# 7segement4digits1badidea-shield-mk-3.net
KiCad netlist of a schematic drawn in EAGLE
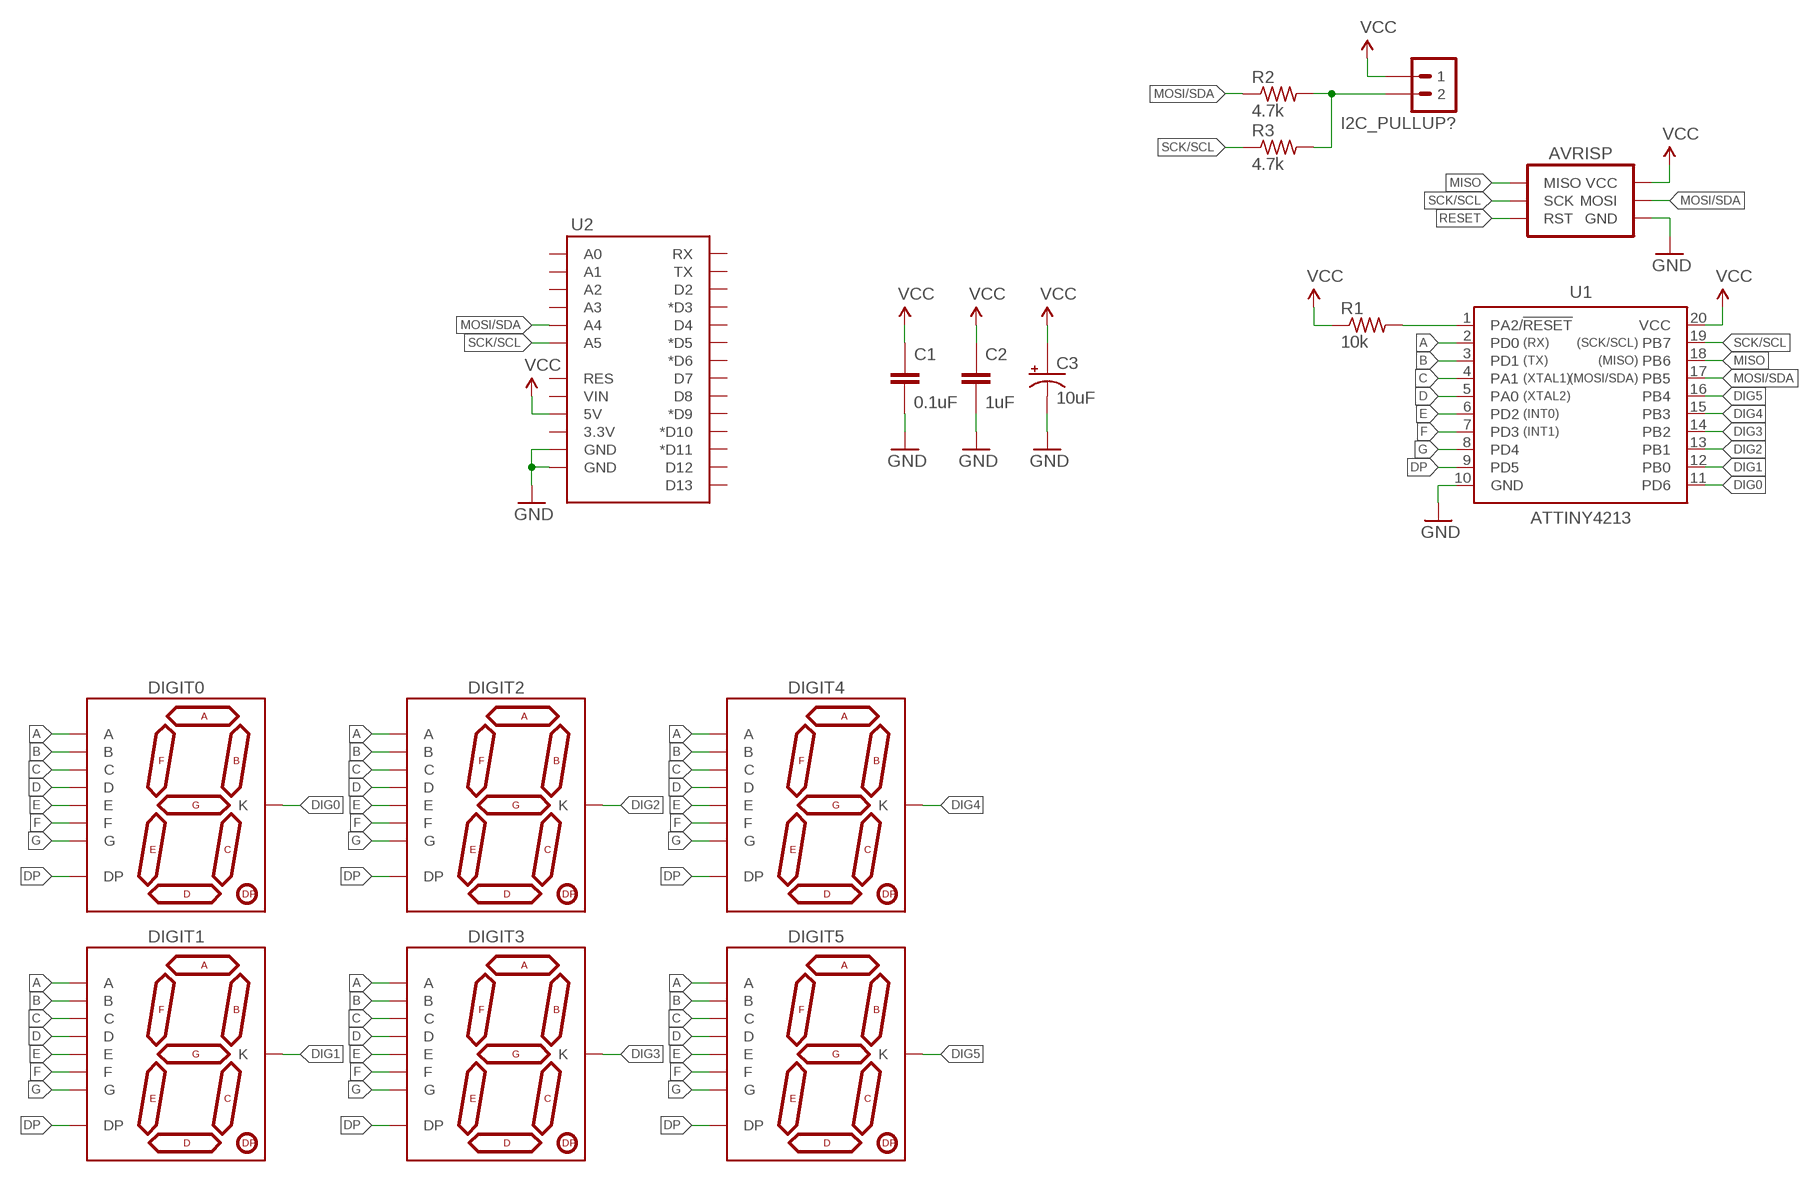
[diagram p0: schematic, sheet 1]

(export (version "E")
  (design (tool "Eeschema 10.0.6"))
  (components
    (comp (ref "AVRISP")
      (value "AVR_SPI_PRG_6PTH")
      (footprint "eagle-import:2X3")
      (libsource (lib "eagle-import") (part "AVR_SPI_PRG_6PTH"))
    )
    (comp (ref "C1")
      (value "0.1uF")
      (footprint "eagle-import:C025-024X044")
      (libsource (lib "eagle-import") (part "CAPACITOR-CERAMIC025-024X044"))
    )
    (comp (ref "C2")
      (value "1uF")
      (footprint "eagle-import:C025-024X044")
      (libsource (lib "eagle-import") (part "CAPACITOR-CERAMIC025-024X044"))
    )
    (comp (ref "C3")
      (value "10uF")
      (footprint "eagle-import:E2,5-5")
      (libsource (lib "eagle-import") (part "CAPACITOR-POLARIZEDE2.5-5"))
    )
    (comp (ref "DIGIT0")
      (value "7SEG_1DIGPTH-10MM")
      (footprint "eagle-import:7SEG_1DIG_10MM")
      (libsource (lib "eagle-import") (part "7SEG_1DIGPTH-10MM"))
    )
    (comp (ref "DIGIT1")
      (value "7SEG_1DIGPTH-10MM")
      (footprint "eagle-import:7SEG_1DIG_10MM")
      (libsource (lib "eagle-import") (part "7SEG_1DIGPTH-10MM"))
    )
    (comp (ref "DIGIT2")
      (value "7SEG_1DIGPTH-10MM")
      (footprint "eagle-import:7SEG_1DIG_10MM")
      (libsource (lib "eagle-import") (part "7SEG_1DIGPTH-10MM"))
    )
    (comp (ref "DIGIT3")
      (value "7SEG_1DIGPTH-10MM")
      (footprint "eagle-import:7SEG_1DIG_10MM")
      (libsource (lib "eagle-import") (part "7SEG_1DIGPTH-10MM"))
    )
    (comp (ref "DIGIT4")
      (value "7SEG_1DIGPTH-10MM")
      (footprint "eagle-import:7SEG_1DIG_10MM")
      (libsource (lib "eagle-import") (part "7SEG_1DIGPTH-10MM"))
    )
    (comp (ref "DIGIT5")
      (value "7SEG_1DIGPTH-10MM")
      (footprint "eagle-import:7SEG_1DIG_10MM")
      (libsource (lib "eagle-import") (part "7SEG_1DIGPTH-10MM"))
    )
    (comp (ref "I2C_PULLUP?")
      (value "M02PTH")
      (footprint "eagle-import:1X02")
      (libsource (lib "eagle-import") (part "M02PTH"))
    )
    (comp (ref "R1")
      (value "10k")
      (footprint "eagle-import:RESISTOR-AXIAL-PTH-7.68MM")
      (libsource (lib "eagle-import") (part "RESISTORPTH-AXIAL-7.68MM"))
    )
    (comp (ref "R2")
      (value "4.7k")
      (footprint "eagle-import:RESISTOR-AXIAL-PTH-7.68MM")
      (libsource (lib "eagle-import") (part "RESISTORPTH-AXIAL-7.68MM"))
    )
    (comp (ref "R3")
      (value "4.7k")
      (footprint "eagle-import:RESISTOR-AXIAL-PTH-7.68MM")
      (libsource (lib "eagle-import") (part "RESISTORPTH-AXIAL-7.68MM"))
    )
    (comp (ref "U1")
      (value "ATTINY4213")
      (footprint "eagle-import:DIL20")
      (libsource (lib "eagle-import") (part "ATTINY2313ADIP"))
    )
    (comp (ref "U2")
      (value "ARDUINO_SHIELD_SMALLER")
      (footprint "eagle-import:ARDUINO_SHIELD_NOOUTLINE_INSIDE_SMALLER")
      (libsource (lib "eagle-import") (part "ARDUINO_SHIELD_SMALLER"))
    )
  )
  (nets
    (net (code "1") (name "A") (class "Default")
      (node (ref "DIGIT0") (pin "10") (pinfunction "A_10") (pintype "bidirectional"))
      (node (ref "DIGIT1") (pin "10") (pinfunction "A_10") (pintype "bidirectional"))
      (node (ref "DIGIT2") (pin "10") (pinfunction "A_10") (pintype "bidirectional"))
      (node (ref "DIGIT3") (pin "10") (pinfunction "A_10") (pintype "bidirectional"))
      (node (ref "DIGIT4") (pin "10") (pinfunction "A_10") (pintype "bidirectional"))
      (node (ref "DIGIT5") (pin "10") (pinfunction "A_10") (pintype "bidirectional"))
      (node (ref "U1") (pin "2") (pinfunction "PD0_2") (pintype "bidirectional"))
    )
    (net (code "2") (name "B") (class "Default")
      (node (ref "DIGIT0") (pin "9") (pinfunction "B_9") (pintype "bidirectional"))
      (node (ref "DIGIT1") (pin "9") (pinfunction "B_9") (pintype "bidirectional"))
      (node (ref "DIGIT2") (pin "9") (pinfunction "B_9") (pintype "bidirectional"))
      (node (ref "DIGIT3") (pin "9") (pinfunction "B_9") (pintype "bidirectional"))
      (node (ref "DIGIT4") (pin "9") (pinfunction "B_9") (pintype "bidirectional"))
      (node (ref "DIGIT5") (pin "9") (pinfunction "B_9") (pintype "bidirectional"))
      (node (ref "U1") (pin "3") (pinfunction "PD1_3") (pintype "bidirectional"))
    )
    (net (code "3") (name "C") (class "Default")
      (node (ref "DIGIT0") (pin "8") (pinfunction "C_8") (pintype "bidirectional"))
      (node (ref "DIGIT1") (pin "8") (pinfunction "C_8") (pintype "bidirectional"))
      (node (ref "DIGIT2") (pin "8") (pinfunction "C_8") (pintype "bidirectional"))
      (node (ref "DIGIT3") (pin "8") (pinfunction "C_8") (pintype "bidirectional"))
      (node (ref "DIGIT4") (pin "8") (pinfunction "C_8") (pintype "bidirectional"))
      (node (ref "DIGIT5") (pin "8") (pinfunction "C_8") (pintype "bidirectional"))
      (node (ref "U1") (pin "4") (pinfunction "PA1_4") (pintype "bidirectional"))
    )
    (net (code "4") (name "D") (class "Default")
      (node (ref "DIGIT0") (pin "5") (pinfunction "D_5") (pintype "bidirectional"))
      (node (ref "DIGIT1") (pin "5") (pinfunction "D_5") (pintype "bidirectional"))
      (node (ref "DIGIT2") (pin "5") (pinfunction "D_5") (pintype "bidirectional"))
      (node (ref "DIGIT3") (pin "5") (pinfunction "D_5") (pintype "bidirectional"))
      (node (ref "DIGIT4") (pin "5") (pinfunction "D_5") (pintype "bidirectional"))
      (node (ref "DIGIT5") (pin "5") (pinfunction "D_5") (pintype "bidirectional"))
      (node (ref "U1") (pin "5") (pinfunction "PA0_5") (pintype "bidirectional"))
    )
    (net (code "5") (name "DIG0") (class "Default")
      (node (ref "DIGIT0") (pin "1") (pinfunction "K_1") (pintype "bidirectional"))
      (node (ref "DIGIT0") (pin "6") (pinfunction "K_6") (pintype "bidirectional"))
      (node (ref "U1") (pin "11") (pinfunction "PD6_11") (pintype "bidirectional"))
    )
    (net (code "6") (name "DIG1") (class "Default")
      (node (ref "DIGIT1") (pin "1") (pinfunction "K_1") (pintype "bidirectional"))
      (node (ref "DIGIT1") (pin "6") (pinfunction "K_6") (pintype "bidirectional"))
      (node (ref "U1") (pin "12") (pinfunction "PB0_12") (pintype "bidirectional"))
    )
    (net (code "7") (name "DIG2") (class "Default")
      (node (ref "DIGIT2") (pin "1") (pinfunction "K_1") (pintype "bidirectional"))
      (node (ref "DIGIT2") (pin "6") (pinfunction "K_6") (pintype "bidirectional"))
      (node (ref "U1") (pin "13") (pinfunction "PB1_13") (pintype "bidirectional"))
    )
    (net (code "8") (name "DIG3") (class "Default")
      (node (ref "DIGIT3") (pin "1") (pinfunction "K_1") (pintype "bidirectional"))
      (node (ref "DIGIT3") (pin "6") (pinfunction "K_6") (pintype "bidirectional"))
      (node (ref "U1") (pin "14") (pinfunction "PB2_14") (pintype "bidirectional"))
    )
    (net (code "9") (name "DIG4") (class "Default")
      (node (ref "DIGIT4") (pin "1") (pinfunction "K_1") (pintype "bidirectional"))
      (node (ref "DIGIT4") (pin "6") (pinfunction "K_6") (pintype "bidirectional"))
      (node (ref "U1") (pin "15") (pinfunction "PB3_15") (pintype "bidirectional"))
    )
    (net (code "10") (name "DIG5") (class "Default")
      (node (ref "DIGIT5") (pin "1") (pinfunction "K_1") (pintype "bidirectional"))
      (node (ref "DIGIT5") (pin "6") (pinfunction "K_6") (pintype "bidirectional"))
      (node (ref "U1") (pin "16") (pinfunction "PB4_16") (pintype "bidirectional"))
    )
    (net (code "11") (name "DP") (class "Default")
      (node (ref "DIGIT0") (pin "7") (pinfunction "DP_7") (pintype "bidirectional"))
      (node (ref "DIGIT1") (pin "7") (pinfunction "DP_7") (pintype "bidirectional"))
      (node (ref "DIGIT2") (pin "7") (pinfunction "DP_7") (pintype "bidirectional"))
      (node (ref "DIGIT3") (pin "7") (pinfunction "DP_7") (pintype "bidirectional"))
      (node (ref "DIGIT4") (pin "7") (pinfunction "DP_7") (pintype "bidirectional"))
      (node (ref "DIGIT5") (pin "7") (pinfunction "DP_7") (pintype "bidirectional"))
      (node (ref "U1") (pin "9") (pinfunction "PD5_9") (pintype "bidirectional"))
    )
    (net (code "12") (name "E") (class "Default")
      (node (ref "DIGIT0") (pin "4") (pinfunction "E_4") (pintype "bidirectional"))
      (node (ref "DIGIT1") (pin "4") (pinfunction "E_4") (pintype "bidirectional"))
      (node (ref "DIGIT2") (pin "4") (pinfunction "E_4") (pintype "bidirectional"))
      (node (ref "DIGIT3") (pin "4") (pinfunction "E_4") (pintype "bidirectional"))
      (node (ref "DIGIT4") (pin "4") (pinfunction "E_4") (pintype "bidirectional"))
      (node (ref "DIGIT5") (pin "4") (pinfunction "E_4") (pintype "bidirectional"))
      (node (ref "U1") (pin "6") (pinfunction "PD2_6") (pintype "bidirectional"))
    )
    (net (code "13") (name "F") (class "Default")
      (node (ref "DIGIT0") (pin "2") (pinfunction "F_2") (pintype "bidirectional"))
      (node (ref "DIGIT1") (pin "2") (pinfunction "F_2") (pintype "bidirectional"))
      (node (ref "DIGIT2") (pin "2") (pinfunction "F_2") (pintype "bidirectional"))
      (node (ref "DIGIT3") (pin "2") (pinfunction "F_2") (pintype "bidirectional"))
      (node (ref "DIGIT4") (pin "2") (pinfunction "F_2") (pintype "bidirectional"))
      (node (ref "DIGIT5") (pin "2") (pinfunction "F_2") (pintype "bidirectional"))
      (node (ref "U1") (pin "7") (pinfunction "PD3_7") (pintype "bidirectional"))
    )
    (net (code "14") (name "G") (class "Default")
      (node (ref "DIGIT0") (pin "3") (pinfunction "G_3") (pintype "bidirectional"))
      (node (ref "DIGIT1") (pin "3") (pinfunction "G_3") (pintype "bidirectional"))
      (node (ref "DIGIT2") (pin "3") (pinfunction "G_3") (pintype "bidirectional"))
      (node (ref "DIGIT3") (pin "3") (pinfunction "G_3") (pintype "bidirectional"))
      (node (ref "DIGIT4") (pin "3") (pinfunction "G_3") (pintype "bidirectional"))
      (node (ref "DIGIT5") (pin "3") (pinfunction "G_3") (pintype "bidirectional"))
      (node (ref "U1") (pin "8") (pinfunction "PD4_8") (pintype "bidirectional"))
    )
    (net (code "15") (name "GND") (class "Default")
      (node (ref "AVRISP") (pin "6") (pinfunction "GND_6") (pintype "passive"))
      (node (ref "C1") (pin "2") (pinfunction "2_2") (pintype "passive"))
      (node (ref "C2") (pin "2") (pinfunction "2_2") (pintype "passive"))
      (node (ref "C3") (pin "-") (pinfunction "-_-") (pintype "passive"))
      (node (ref "U1") (pin "10") (pinfunction "GND_10") (pintype "bidirectional"))
      (node (ref "U2") (pin "GND@0") (pinfunction "GND_GND@0") (pintype "bidirectional"))
      (node (ref "U2") (pin "GND@1") (pinfunction "GND_GND@1") (pintype "bidirectional"))
    )
    (net (code "16") (name "MISO") (class "Default")
      (node (ref "AVRISP") (pin "1") (pinfunction "MISO_1") (pintype "passive"))
      (node (ref "U1") (pin "18") (pinfunction "PB6_18") (pintype "bidirectional"))
    )
    (net (code "17") (name "MOSI{slash}SDA") (class "Default")
      (node (ref "AVRISP") (pin "4") (pinfunction "MOSI_4") (pintype "passive"))
      (node (ref "R2") (pin "P$1") (pinfunction "1_P$1") (pintype "passive"))
      (node (ref "U1") (pin "17") (pinfunction "PB5_17") (pintype "bidirectional"))
      (node (ref "U2") (pin "A4") (pinfunction "A4_A4") (pintype "bidirectional"))
    )
    (net (code "18") (name "Net-(R1-2)") (class "Default")
      (node (ref "R1") (pin "P$2") (pinfunction "2_P$2") (pintype "passive"))
      (node (ref "U1") (pin "1") (pinfunction "PA2/~{RESET}_1") (pintype "bidirectional"))
    )
    (net (code "19") (name "Net-(R2-2)") (class "Default")
      (node (ref "I2C_PULLUP?") (pin "2") (pinfunction "2_2") (pintype "passive"))
      (node (ref "R2") (pin "P$2") (pinfunction "2_P$2") (pintype "passive"))
      (node (ref "R3") (pin "P$2") (pinfunction "2_P$2") (pintype "passive"))
    )
    (net (code "20") (name "RESET") (class "Default")
      (node (ref "AVRISP") (pin "5") (pinfunction "RST_5") (pintype "passive"))
    )
    (net (code "21") (name "SCK{slash}SCL") (class "Default")
      (node (ref "AVRISP") (pin "3") (pinfunction "SCK_3") (pintype "passive"))
      (node (ref "R3") (pin "P$1") (pinfunction "1_P$1") (pintype "passive"))
      (node (ref "U1") (pin "19") (pinfunction "PB7_19") (pintype "bidirectional"))
      (node (ref "U2") (pin "A5") (pinfunction "A5_A5") (pintype "bidirectional"))
    )
    (net (code "22") (name "VCC") (class "Default")
      (node (ref "AVRISP") (pin "2") (pinfunction "VCC_2") (pintype "passive"))
      (node (ref "C1") (pin "1") (pinfunction "1_1") (pintype "passive"))
      (node (ref "C2") (pin "1") (pinfunction "1_1") (pintype "passive"))
      (node (ref "C3") (pin "+") (pinfunction "+_+") (pintype "passive"))
      (node (ref "I2C_PULLUP?") (pin "1") (pinfunction "1_1") (pintype "passive"))
      (node (ref "R1") (pin "P$1") (pinfunction "1_P$1") (pintype "passive"))
      (node (ref "U1") (pin "20") (pinfunction "VCC_20") (pintype "bidirectional"))
      (node (ref "U2") (pin "5V") (pinfunction "5V_5V") (pintype "bidirectional"))
    )
    (net (code "23") (name "unconnected-(U2-*D3-PadD3)") (class "Default")
      (node (ref "U2") (pin "D3") (pinfunction "*D3_D3") (pintype "bidirectional"))
    )
    (net (code "24") (name "unconnected-(U2-*D5-PadD5)") (class "Default")
      (node (ref "U2") (pin "D5") (pinfunction "*D5_D5") (pintype "bidirectional"))
    )
    (net (code "25") (name "unconnected-(U2-*D6-PadD6)") (class "Default")
      (node (ref "U2") (pin "D6") (pinfunction "*D6_D6") (pintype "bidirectional"))
    )
    (net (code "26") (name "unconnected-(U2-*D9-PadD9)") (class "Default")
      (node (ref "U2") (pin "D9") (pinfunction "*D9_D9") (pintype "bidirectional"))
    )
    (net (code "27") (name "unconnected-(U2-*D10-PadD10)") (class "Default")
      (node (ref "U2") (pin "D10") (pinfunction "*D10_D10") (pintype "bidirectional"))
    )
    (net (code "28") (name "unconnected-(U2-*D11-PadD11)") (class "Default")
      (node (ref "U2") (pin "D11") (pinfunction "*D11_D11") (pintype "bidirectional"))
    )
    (net (code "29") (name "unconnected-(U2-Pad3.3V)") (class "Default")
      (node (ref "U2") (pin "3.3V") (pinfunction "3.3V_3.3V") (pintype "bidirectional"))
    )
    (net (code "30") (name "unconnected-(U2-PadA0)") (class "Default")
      (node (ref "U2") (pin "A0") (pinfunction "A0_A0") (pintype "bidirectional"))
    )
    (net (code "31") (name "unconnected-(U2-PadA1)") (class "Default")
      (node (ref "U2") (pin "A1") (pinfunction "A1_A1") (pintype "bidirectional"))
    )
    (net (code "32") (name "unconnected-(U2-PadA2)") (class "Default")
      (node (ref "U2") (pin "A2") (pinfunction "A2_A2") (pintype "bidirectional"))
    )
    (net (code "33") (name "unconnected-(U2-PadA3)") (class "Default")
      (node (ref "U2") (pin "A3") (pinfunction "A3_A3") (pintype "bidirectional"))
    )
    (net (code "34") (name "unconnected-(U2-PadD2)") (class "Default")
      (node (ref "U2") (pin "D2") (pinfunction "D2_D2") (pintype "bidirectional"))
    )
    (net (code "35") (name "unconnected-(U2-PadD4)") (class "Default")
      (node (ref "U2") (pin "D4") (pinfunction "D4_D4") (pintype "bidirectional"))
    )
    (net (code "36") (name "unconnected-(U2-PadD7)") (class "Default")
      (node (ref "U2") (pin "D7") (pinfunction "D7_D7") (pintype "bidirectional"))
    )
    (net (code "37") (name "unconnected-(U2-PadD8)") (class "Default")
      (node (ref "U2") (pin "D8") (pinfunction "D8_D8") (pintype "bidirectional"))
    )
    (net (code "38") (name "unconnected-(U2-PadD12)") (class "Default")
      (node (ref "U2") (pin "D12") (pinfunction "D12_D12") (pintype "bidirectional"))
    )
    (net (code "39") (name "unconnected-(U2-PadD13)") (class "Default")
      (node (ref "U2") (pin "D13") (pinfunction "D13_D13") (pintype "bidirectional"))
    )
    (net (code "40") (name "unconnected-(U2-PadRES)") (class "Default")
      (node (ref "U2") (pin "RES") (pinfunction "RES_RES") (pintype "bidirectional"))
    )
    (net (code "41") (name "unconnected-(U2-PadRX)") (class "Default")
      (node (ref "U2") (pin "RX") (pinfunction "RX_RX") (pintype "bidirectional"))
    )
    (net (code "42") (name "unconnected-(U2-PadTX)") (class "Default")
      (node (ref "U2") (pin "TX") (pinfunction "TX_TX") (pintype "bidirectional"))
    )
    (net (code "43") (name "unconnected-(U2-PadVIN)") (class "Default")
      (node (ref "U2") (pin "VIN") (pinfunction "VIN_VIN") (pintype "bidirectional"))
    )
  )
)
